# Sensor.net
KiCad netlist of a schematic drawn in Altium Designer
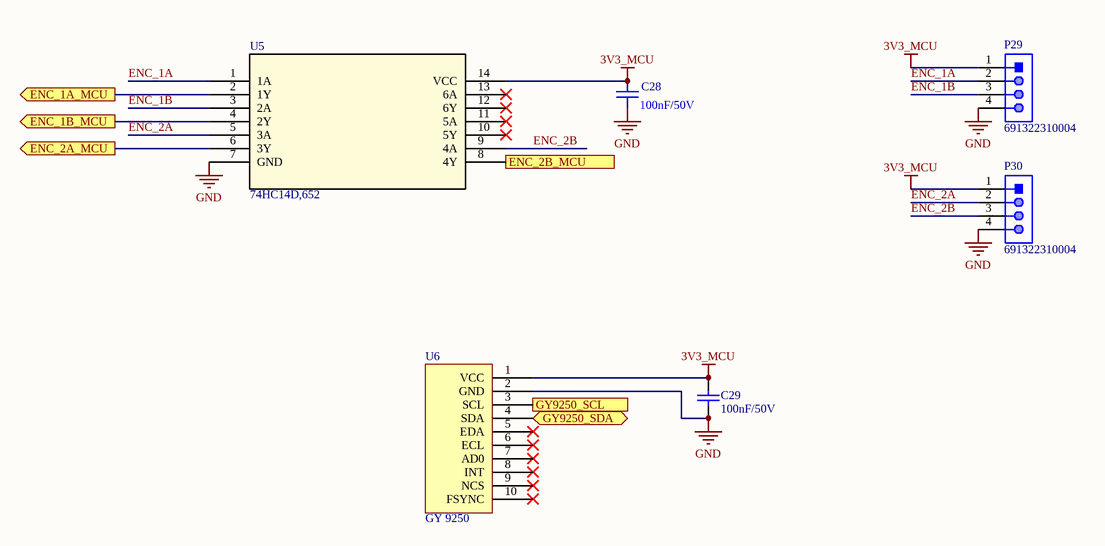
[diagram p0: Sensor.SchDoc]

(export (version "E")
  (design (tool "Eeschema 10.0.6"))
  (components
    (comp (ref "C28")
      (value "100nF/50V")
      (footprint "CAP-SM-0805")
      (description "Capacitor")
      (fields (field (name "Comment") "Cap Non-Pol SMD"))
      (libsource (lib "PIF_C16_lib") (part "Cap Non-Pol SMD"))
    )
    (comp (ref "C29")
      (value "100nF/50V")
      (footprint "CAP-SM-0805")
      (description "CAP CER 1000PF 100V X7R 0805")
      (fields
        (field (name "MANUFACTURER") "Johanson Dielectrics Inc.")
        (field (name "MANUFACTURER PART NUMBER") "101X15W102MV4E")
      )
      (libsource (lib "Capacitor") (part "Cap-1nF-50V-0805"))
    )
    (comp (ref "P29")
      (value "691322310004")
      (footprint "691322310004")
      (description "WR-TBL Serie 322 Horizontal PCB Header, Pluggable, pitch 3.81mm, 4p")
      (fields (field (name "PUBLISHER") "Wurth Elektronik"))
      (libsource (lib "691101710002_Altium_WR-TBL_rev19a") (part "691322310004"))
    )
    (comp (ref "P30")
      (value "691322310004")
      (footprint "691322310004")
      (description "WR-TBL Serie 322 Horizontal PCB Header, Pluggable, pitch 3.81mm, 4p")
      (fields (field (name "PUBLISHER") "Wurth Elektronik"))
      (libsource (lib "691101710002_Altium_WR-TBL_rev19a") (part "691322310004"))
    )
    (comp (ref "U5")
      (value "74HC14D,652")
      (footprint "74HC14D,652")
      (fields (field (name "COPYRIGHT") "Copyright (C) 2016 Accelerated Designs. All rights reserved"))
      (libsource (lib "Integrated_Library") (part "74HC14D,652"))
    )
    (comp (ref "U6")
      (value "GY 9250")
      (footprint "GY 9250")
      (libsource (lib "Integrated_Library") (part "GY 9250"))
    )
  )
  (nets
    (net (code "1") (name "/ENC_1A") (class "Default")
      (node (ref "P29") (pin "2") (pinfunction "2_2") (pintype "passive"))
      (node (ref "U5") (pin "1") (pinfunction "1A_1") (pintype "open_collector"))
    )
    (net (code "2") (name "/ENC_1A_MCU") (class "Default")
      (node (ref "U5") (pin "2") (pinfunction "1Y_2") (pintype "open_collector"))
    )
    (net (code "3") (name "/ENC_1B") (class "Default")
      (node (ref "P29") (pin "3") (pinfunction "3_3") (pintype "passive"))
      (node (ref "U5") (pin "3") (pinfunction "2A_3") (pintype "open_collector"))
    )
    (net (code "4") (name "/ENC_1B_MCU") (class "Default")
      (node (ref "U5") (pin "4") (pinfunction "2Y_4") (pintype "open_collector"))
    )
    (net (code "5") (name "/ENC_2A") (class "Default")
      (node (ref "P30") (pin "2") (pinfunction "2_2") (pintype "passive"))
      (node (ref "U5") (pin "5") (pinfunction "3A_5") (pintype "open_collector"))
    )
    (net (code "6") (name "/ENC_2A_MCU") (class "Default")
      (node (ref "U5") (pin "6") (pinfunction "3Y_6") (pintype "open_collector"))
    )
    (net (code "7") (name "/ENC_2B") (class "Default")
      (node (ref "P30") (pin "3") (pinfunction "3_3") (pintype "passive"))
      (node (ref "U5") (pin "9") (pinfunction "4A_9") (pintype "open_collector"))
    )
    (net (code "8") (name "/ENC_2B_MCU") (class "Default")
      (node (ref "U5") (pin "8") (pinfunction "4Y_8") (pintype "open_collector"))
    )
    (net (code "9") (name "/GY9250_SCL") (class "Default")
      (node (ref "U6") (pin "3") (pinfunction "SCL_3") (pintype "passive"))
    )
    (net (code "10") (name "/GY9250_SDA") (class "Default")
      (node (ref "U6") (pin "4") (pinfunction "SDA_4") (pintype "passive"))
    )
    (net (code "11") (name "3V3_MCU") (class "Default")
      (node (ref "C28") (pin "2") (pinfunction "2_2") (pintype "passive"))
      (node (ref "C29") (pin "2") (pinfunction "2_2") (pintype "passive"))
      (node (ref "P29") (pin "1") (pinfunction "1_1") (pintype "passive"))
      (node (ref "P30") (pin "1") (pinfunction "1_1") (pintype "passive"))
      (node (ref "U5") (pin "14") (pinfunction "VCC_14") (pintype "open_collector"))
      (node (ref "U6") (pin "1") (pinfunction "VCC_1") (pintype "passive"))
    )
    (net (code "12") (name "GND") (class "Default")
      (node (ref "C28") (pin "1") (pinfunction "1_1") (pintype "passive"))
      (node (ref "C29") (pin "1") (pinfunction "1_1") (pintype "passive"))
      (node (ref "P29") (pin "4") (pinfunction "4_4") (pintype "passive"))
      (node (ref "P30") (pin "4") (pinfunction "4_4") (pintype "passive"))
      (node (ref "U5") (pin "7") (pinfunction "GND_7") (pintype "open_collector"))
      (node (ref "U6") (pin "2") (pinfunction "GND_2") (pintype "passive"))
    )
    (net (code "13") (name "unconnected-(U5-5A-Pad11)") (class "Default")
      (node (ref "U5") (pin "11") (pinfunction "5A_11") (pintype "open_collector+no_connect"))
    )
    (net (code "14") (name "unconnected-(U5-5Y-Pad10)") (class "Default")
      (node (ref "U5") (pin "10") (pinfunction "5Y_10") (pintype "open_collector+no_connect"))
    )
    (net (code "15") (name "unconnected-(U5-6A-Pad13)") (class "Default")
      (node (ref "U5") (pin "13") (pinfunction "6A_13") (pintype "open_collector+no_connect"))
    )
    (net (code "16") (name "unconnected-(U5-6Y-Pad12)") (class "Default")
      (node (ref "U5") (pin "12") (pinfunction "6Y_12") (pintype "open_collector+no_connect"))
    )
    (net (code "17") (name "unconnected-(U6-AD0-Pad7)") (class "Default")
      (node (ref "U6") (pin "7") (pinfunction "AD0_7") (pintype "passive+no_connect"))
    )
    (net (code "18") (name "unconnected-(U6-ECL-Pad6)") (class "Default")
      (node (ref "U6") (pin "6") (pinfunction "ECL_6") (pintype "passive+no_connect"))
    )
    (net (code "19") (name "unconnected-(U6-EDA-Pad5)") (class "Default")
      (node (ref "U6") (pin "5") (pinfunction "EDA_5") (pintype "passive+no_connect"))
    )
    (net (code "20") (name "unconnected-(U6-FSYNC-Pad10)") (class "Default")
      (node (ref "U6") (pin "10") (pinfunction "FSYNC_10") (pintype "passive+no_connect"))
    )
    (net (code "21") (name "unconnected-(U6-INT-Pad8)") (class "Default")
      (node (ref "U6") (pin "8") (pinfunction "INT_8") (pintype "passive+no_connect"))
    )
    (net (code "22") (name "unconnected-(U6-NCS-Pad9)") (class "Default")
      (node (ref "U6") (pin "9") (pinfunction "NCS_9") (pintype "passive+no_connect"))
    )
  )
)
